# graduation_project.net
KiCad netlist of a schematic drawn in Altium Designer
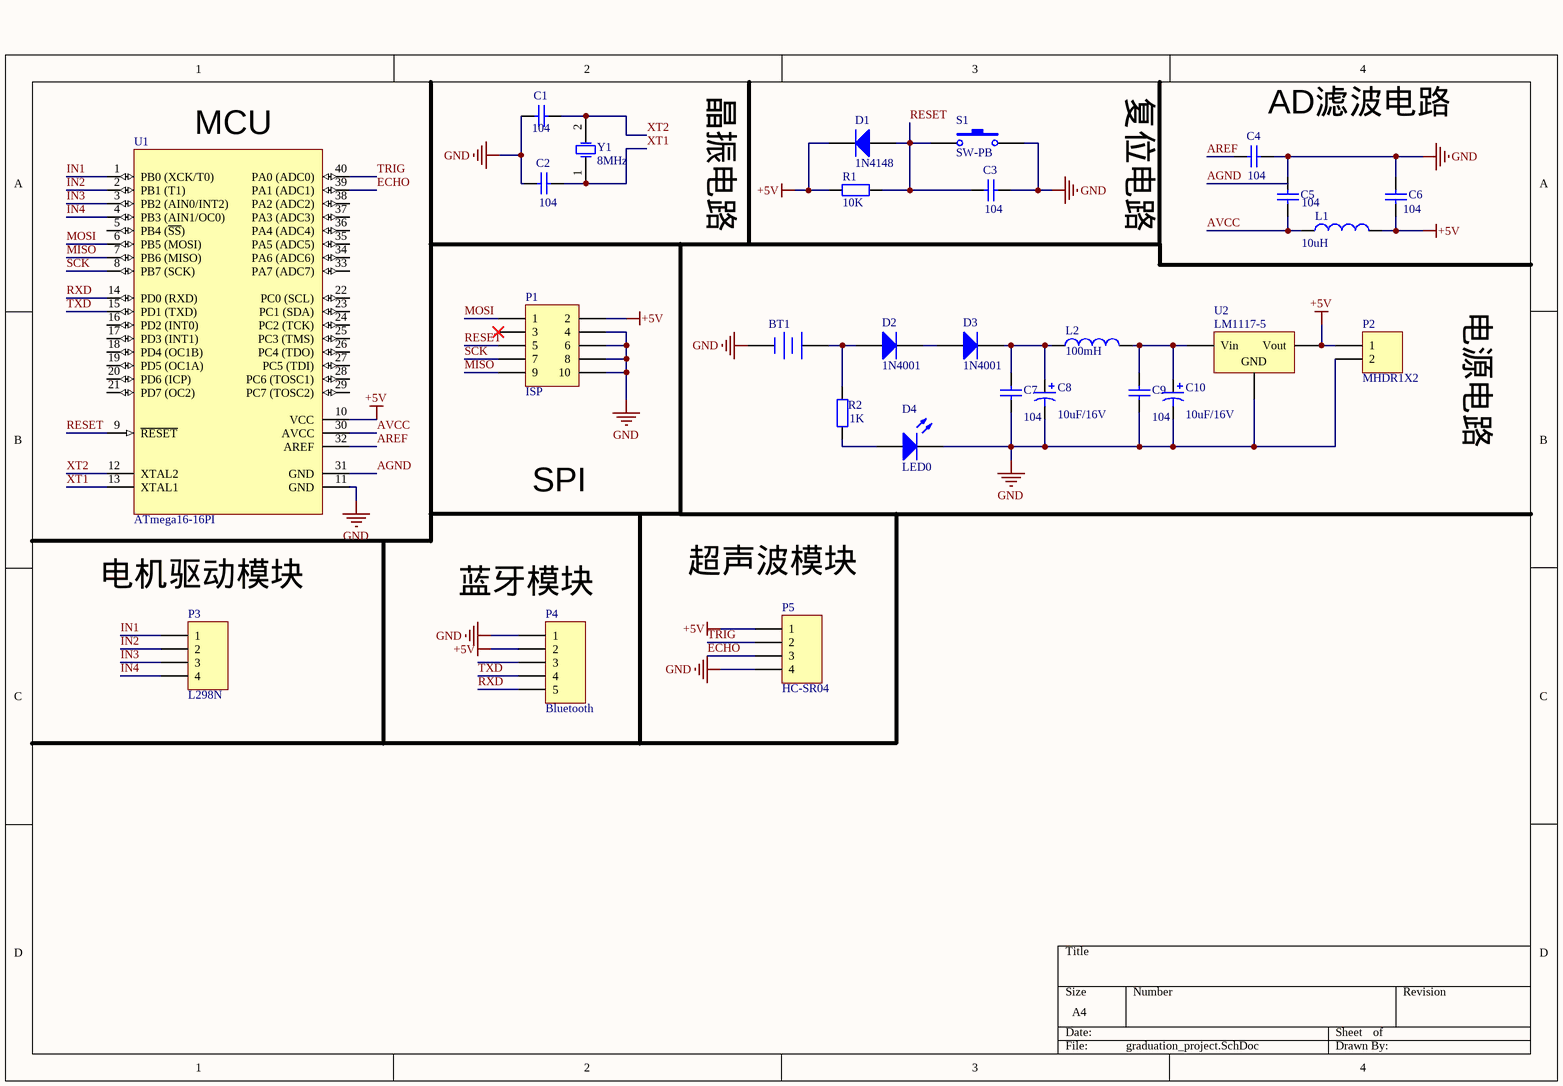
[diagram p0: graduation_project.SchDoc]

(export (version "E")
  (design (tool "Eeschema 10.0.6"))
  (components
    (comp (ref "BT1")
      (value "Battery")
      (footprint "DC10B")
      (description "Multicell Battery")
      (fields (field (name "PUBLISHER") "Altium Limited"))
      (libsource (lib "Miscellaneous Devices") (part "Battery"))
    )
    (comp (ref "C1")
      (value "104")
      (footprint "C0805")
      (description "Capacitor")
      (fields (field (name "Comment") "Cap") (field (name "PUBLISHER") "Altium Limited"))
      (libsource (lib "Miscellaneous Devices") (part "Cap"))
    )
    (comp (ref "C2")
      (value "104")
      (footprint "C0805")
      (description "Capacitor")
      (fields (field (name "Comment") "Cap") (field (name "PUBLISHER") "Altium Limited"))
      (libsource (lib "Miscellaneous Devices") (part "Cap"))
    )
    (comp (ref "C3")
      (value "104")
      (footprint "C0805")
      (description "Capacitor")
      (fields (field (name "Comment") "Cap") (field (name "PUBLISHER") "Altium Limited"))
      (libsource (lib "Miscellaneous Devices") (part "Cap"))
    )
    (comp (ref "C4")
      (value "104")
      (footprint "C0805")
      (description "Capacitor")
      (fields (field (name "Comment") "Cap") (field (name "PUBLISHER") "Altium Limited"))
      (libsource (lib "Miscellaneous Devices") (part "Cap"))
    )
    (comp (ref "C5")
      (value "104")
      (footprint "C0805")
      (description "Capacitor")
      (fields (field (name "Comment") "Cap") (field (name "PUBLISHER") "Altium Limited"))
      (libsource (lib "Miscellaneous Devices") (part "Cap"))
    )
    (comp (ref "C6")
      (value "104")
      (footprint "C0805")
      (description "Capacitor")
      (fields (field (name "Comment") "Cap") (field (name "PUBLISHER") "Altium Limited"))
      (libsource (lib "Miscellaneous Devices") (part "Cap"))
    )
    (comp (ref "C7")
      (value "104")
      (footprint "C0805")
      (description "Capacitor")
      (fields (field (name "Comment") "Cap") (field (name "PUBLISHER") "Altium Limited"))
      (libsource (lib "Miscellaneous Devices") (part "Cap"))
    )
    (comp (ref "C8")
      (value "10uF/16V")
      (footprint "CAP5*5_4")
      (description "Polarized Capacitor (Surface Mount)")
      (fields (field (name "Comment") "Cap Pol3") (field (name "PUBLISHER") "Altium Limited"))
      (libsource (lib "Miscellaneous Devices") (part "Cap Pol3"))
    )
    (comp (ref "C9")
      (value "104")
      (footprint "C0805")
      (description "Capacitor")
      (fields (field (name "Comment") "Cap") (field (name "PUBLISHER") "Altium Limited"))
      (libsource (lib "Miscellaneous Devices") (part "Cap"))
    )
    (comp (ref "C10")
      (value "10uF/16V")
      (footprint "CAP5*5_4")
      (description "Polarized Capacitor (Surface Mount)")
      (fields (field (name "Comment") "Cap Pol3") (field (name "PUBLISHER") "Altium Limited"))
      (libsource (lib "Miscellaneous Devices") (part "Cap Pol3"))
    )
    (comp (ref "D1")
      (value "1N4148")
      (footprint "1N4148-T")
      (description "Default Diode")
      (fields (field (name "PUBLISHER") "Altium Limited"))
      (libsource (lib "Miscellaneous Devices") (part "Diode"))
    )
    (comp (ref "D2")
      (value "1N4001")
      (footprint "1N4148-T")
      (description "Default Diode")
      (fields (field (name "PUBLISHER") "Altium Limited"))
      (libsource (lib "Miscellaneous Devices") (part "Diode"))
    )
    (comp (ref "D3")
      (value "1N4001")
      (footprint "1N4148-T")
      (description "Default Diode")
      (fields (field (name "PUBLISHER") "Altium Limited"))
      (libsource (lib "Miscellaneous Devices") (part "Diode"))
    )
    (comp (ref "D4")
      (value "LED0")
      (footprint "LED1206")
      (description "Typical INFRARED GaAs LED")
      (fields (field (name "PUBLISHER") "Altium Limited"))
      (libsource (lib "Miscellaneous Devices") (part "LED0"))
    )
    (comp (ref "L1")
      (value "10uH")
      (footprint "R0805")
      (description "Inductor")
      (fields (field (name "PUBLISHER") "Altium Limited"))
      (libsource (lib "Miscellaneous Devices") (part "Inductor"))
    )
    (comp (ref "L2")
      (value "100mH")
      (footprint "R0805")
      (description "Inductor")
      (fields (field (name "PUBLISHER") "Altium Limited"))
      (libsource (lib "Miscellaneous Devices") (part "Inductor"))
    )
    (comp (ref "P1")
      (value "ISP")
      (footprint "MHDR2X5")
      (description "Header, 5-Pin, Dual row")
      (fields (field (name "PUBLISHER") "Altium Limited"))
      (libsource (lib "Miscellaneous Connectors") (part "MHDR2X5"))
    )
    (comp (ref "P2")
      (value "MHDR1X2")
      (footprint "MHDR1X2")
      (description "Header, 2-Pin")
      (fields (field (name "PUBLISHER") "Altium Limited"))
      (libsource (lib "Miscellaneous Connectors") (part "MHDR1X2"))
    )
    (comp (ref "P3")
      (value "L298N")
      (footprint "MHDR1X4")
      (description "Header, 4-Pin")
      (fields (field (name "PUBLISHER") "Altium Limited"))
      (libsource (lib "Miscellaneous Connectors") (part "MHDR1X4"))
    )
    (comp (ref "P4")
      (value "Bluetooth")
      (footprint "MHDR1X5")
      (description "Header, 5-Pin")
      (fields (field (name "PUBLISHER") "Altium Limited"))
      (libsource (lib "Miscellaneous Connectors") (part "MHDR1X5"))
    )
    (comp (ref "P5")
      (value "HC-SR04")
      (footprint "MHDR1X4")
      (description "Header, 4-Pin")
      (fields (field (name "PUBLISHER") "Altium Limited"))
      (libsource (lib "Miscellaneous Connectors") (part "MHDR1X4"))
    )
    (comp (ref "R1")
      (value "10K")
      (footprint "R0805")
      (description "Resistor")
      (fields (field (name "Comment") "Res2") (field (name "PUBLISHER") "Altium Limited"))
      (libsource (lib "") (part "Res2_1"))
    )
    (comp (ref "R2")
      (value "1K")
      (footprint "R0805")
      (description "Resistor")
      (fields (field (name "Comment") "Res2") (field (name "PUBLISHER") "Altium Limited"))
      (libsource (lib "Miscellaneous Devices") (part "Res2"))
    )
    (comp (ref "S1")
      (value "SW-PB")
      (footprint "SWITCH")
      (description "Switch")
      (fields (field (name "PUBLISHER") "Altium Limited"))
      (libsource (lib "Miscellaneous Devices") (part "SW-PB"))
    )
    (comp (ref "U1")
      (value "ATmega16-16PI")
      (footprint "40P6")
      (description "8-Bit AVR Microcontroller with 16K Bytes of In-System Programmable Flash Memory")
      (fields (field (name "PUBLISHER") "Altium Limited"))
      (libsource (lib "Atmel Microcontroller 8-Bit AVR") (part "ATmega16-16PI"))
    )
    (comp (ref "U2")
      (value "LM1117-5")
      (footprint "SOT223")
      (description "Voltage Regulator")
      (fields (field (name "PUBLISHER") "Altium Limited"))
      (libsource (lib "Miscellaneous Devices") (part "Volt Reg"))
    )
    (comp (ref "Y1")
      (value "8MHz")
      (footprint "XTAL")
      (description "Crystal Oscillator")
      (fields (field (name "PUBLISHER") "Altium Limited"))
      (libsource (lib "Miscellaneous Devices") (part "XTAL"))
    )
  )
  (nets
    (net (code "1") (name "+5V") (class "Default")
      (node (ref "C6") (pin "2") (pinfunction "2_2") (pintype "passive"))
      (node (ref "D1") (pin "2") (pinfunction "K_2") (pintype "passive"))
      (node (ref "L1") (pin "2") (pinfunction "2_2") (pintype "passive"))
      (node (ref "P1") (pin "2") (pinfunction "2_2") (pintype "passive"))
      (node (ref "P2") (pin "1") (pinfunction "1_1") (pintype "passive"))
      (node (ref "P4") (pin "2") (pinfunction "2_2") (pintype "passive"))
      (node (ref "P5") (pin "1") (pinfunction "1_1") (pintype "passive"))
      (node (ref "R1") (pin "1") (pinfunction "1_1") (pintype "passive"))
      (node (ref "U1") (pin "10") (pinfunction "VCC_10") (pintype "power_in"))
      (node (ref "U2") (pin "3") (pinfunction "Vout_3") (pintype "passive"))
    )
    (net (code "2") (name "/AGND") (class "Default")
      (node (ref "U1") (pin "31") (pinfunction "GND_31") (pintype "power_in"))
    )
    (net (code "3") (name "/AREF") (class "Default")
      (node (ref "C4") (pin "2") (pinfunction "2_2") (pintype "passive"))
      (node (ref "U1") (pin "32") (pinfunction "AREF_32") (pintype "passive"))
    )
    (net (code "4") (name "/AVCC") (class "Default")
      (node (ref "C5") (pin "2") (pinfunction "2_2") (pintype "passive"))
      (node (ref "L1") (pin "1") (pinfunction "1_1") (pintype "passive"))
      (node (ref "U1") (pin "30") (pinfunction "AVCC_30") (pintype "power_in"))
    )
    (net (code "5") (name "/ECHO") (class "Default")
      (node (ref "P5") (pin "3") (pinfunction "3_3") (pintype "passive"))
      (node (ref "U1") (pin "39") (pinfunction "PA1_(ADC1)_39") (pintype "bidirectional"))
    )
    (net (code "6") (name "/IN1") (class "Default")
      (node (ref "P3") (pin "1") (pinfunction "1_1") (pintype "passive"))
      (node (ref "U1") (pin "1") (pinfunction "PB0_(XCK/T0)_1") (pintype "bidirectional"))
    )
    (net (code "7") (name "/IN2") (class "Default")
      (node (ref "P3") (pin "2") (pinfunction "2_2") (pintype "passive"))
      (node (ref "U1") (pin "2") (pinfunction "PB1_(T1)_2") (pintype "bidirectional"))
    )
    (net (code "8") (name "/IN3") (class "Default")
      (node (ref "P3") (pin "3") (pinfunction "3_3") (pintype "passive"))
      (node (ref "U1") (pin "3") (pinfunction "PB2_(AIN0/INT2)_3") (pintype "bidirectional"))
    )
    (net (code "9") (name "/IN4") (class "Default")
      (node (ref "P3") (pin "4") (pinfunction "4_4") (pintype "passive"))
      (node (ref "U1") (pin "4") (pinfunction "PB3_(AIN1/OC0)_4") (pintype "bidirectional"))
    )
    (net (code "10") (name "/MISO") (class "Default")
      (node (ref "P1") (pin "9") (pinfunction "9_9") (pintype "passive"))
      (node (ref "U1") (pin "7") (pinfunction "PB6_(MISO)_7") (pintype "bidirectional"))
    )
    (net (code "11") (name "/MOSI") (class "Default")
      (node (ref "P1") (pin "1") (pinfunction "1_1") (pintype "passive"))
      (node (ref "U1") (pin "6") (pinfunction "PB5_(MOSI)_6") (pintype "bidirectional"))
    )
    (net (code "12") (name "/RESET") (class "Default")
      (node (ref "C3") (pin "1") (pinfunction "1_1") (pintype "passive"))
      (node (ref "D1") (pin "1") (pinfunction "A_1") (pintype "passive"))
      (node (ref "P1") (pin "5") (pinfunction "5_5") (pintype "passive"))
      (node (ref "R1") (pin "2") (pinfunction "2_2") (pintype "passive"))
      (node (ref "S1") (pin "1") (pinfunction "1_1") (pintype "passive"))
      (node (ref "U1") (pin "9") (pinfunction "~{RESET}_9") (pintype "input"))
    )
    (net (code "13") (name "/RXD") (class "Default")
      (node (ref "P4") (pin "5") (pinfunction "5_5") (pintype "passive"))
      (node (ref "U1") (pin "14") (pinfunction "PD0_(RXD)_14") (pintype "bidirectional"))
    )
    (net (code "14") (name "/SCK") (class "Default")
      (node (ref "P1") (pin "7") (pinfunction "7_7") (pintype "passive"))
      (node (ref "U1") (pin "8") (pinfunction "PB7_(SCK)_8") (pintype "bidirectional"))
    )
    (net (code "15") (name "/TRIG") (class "Default")
      (node (ref "P5") (pin "2") (pinfunction "2_2") (pintype "passive"))
      (node (ref "U1") (pin "40") (pinfunction "PA0_(ADC0)_40") (pintype "bidirectional"))
    )
    (net (code "16") (name "/TXD") (class "Default")
      (node (ref "P4") (pin "4") (pinfunction "4_4") (pintype "passive"))
      (node (ref "U1") (pin "15") (pinfunction "PD1_(TXD)_15") (pintype "bidirectional"))
    )
    (net (code "17") (name "/XT1") (class "Default")
      (node (ref "C2") (pin "2") (pinfunction "2_2") (pintype "passive"))
      (node (ref "U1") (pin "13") (pinfunction "XTAL1_13") (pintype "passive"))
      (node (ref "Y1") (pin "1") (pinfunction "OSC1_1") (pintype "passive"))
    )
    (net (code "18") (name "/XT2") (class "Default")
      (node (ref "C1") (pin "2") (pinfunction "2_2") (pintype "passive"))
      (node (ref "U1") (pin "12") (pinfunction "XTAL2_12") (pintype "passive"))
      (node (ref "Y1") (pin "2") (pinfunction "OSC2_2") (pintype "passive"))
    )
    (net (code "19") (name "GND") (class "Default")
      (node (ref "BT1") (pin "2") (pinfunction "-_2") (pintype "passive"))
      (node (ref "C1") (pin "1") (pinfunction "1_1") (pintype "passive"))
      (node (ref "C10") (pin "2") (pinfunction "2_2") (pintype "passive"))
      (node (ref "C2") (pin "1") (pinfunction "1_1") (pintype "passive"))
      (node (ref "C3") (pin "2") (pinfunction "2_2") (pintype "passive"))
      (node (ref "C4") (pin "1") (pinfunction "1_1") (pintype "passive"))
      (node (ref "C5") (pin "1") (pinfunction "1_1") (pintype "passive"))
      (node (ref "C6") (pin "1") (pinfunction "1_1") (pintype "passive"))
      (node (ref "C7") (pin "1") (pinfunction "1_1") (pintype "passive"))
      (node (ref "C8") (pin "2") (pinfunction "2_2") (pintype "passive"))
      (node (ref "C9") (pin "1") (pinfunction "1_1") (pintype "passive"))
      (node (ref "D4") (pin "2") (pinfunction "K_2") (pintype "passive"))
      (node (ref "P1") (pin "10") (pinfunction "10_10") (pintype "passive"))
      (node (ref "P1") (pin "4") (pinfunction "4_4") (pintype "passive"))
      (node (ref "P1") (pin "6") (pinfunction "6_6") (pintype "passive"))
      (node (ref "P1") (pin "8") (pinfunction "8_8") (pintype "passive"))
      (node (ref "P2") (pin "2") (pinfunction "2_2") (pintype "passive"))
      (node (ref "P4") (pin "1") (pinfunction "1_1") (pintype "passive"))
      (node (ref "P5") (pin "4") (pinfunction "4_4") (pintype "passive"))
      (node (ref "S1") (pin "2") (pinfunction "2_2") (pintype "passive"))
      (node (ref "U1") (pin "11") (pinfunction "GND_11") (pintype "power_in"))
      (node (ref "U2") (pin "2") (pinfunction "GND_2") (pintype "passive"))
    )
    (net (code "20") (name "Net-(BT1-+)") (class "Default")
      (node (ref "BT1") (pin "1") (pinfunction "+_1") (pintype "passive"))
      (node (ref "D2") (pin "1") (pinfunction "A_1") (pintype "passive"))
      (node (ref "R2") (pin "1") (pinfunction "1_1") (pintype "passive"))
    )
    (net (code "21") (name "Net-(D2-K)") (class "Default")
      (node (ref "D2") (pin "2") (pinfunction "K_2") (pintype "passive"))
      (node (ref "D3") (pin "1") (pinfunction "A_1") (pintype "passive"))
    )
    (net (code "22") (name "Net-(D3-K)") (class "Default")
      (node (ref "C7") (pin "2") (pinfunction "2_2") (pintype "passive"))
      (node (ref "C8") (pin "1") (pinfunction "1_1") (pintype "passive"))
      (node (ref "D3") (pin "2") (pinfunction "K_2") (pintype "passive"))
      (node (ref "L2") (pin "1") (pinfunction "1_1") (pintype "passive"))
    )
    (net (code "23") (name "Net-(D4-A)") (class "Default")
      (node (ref "D4") (pin "1") (pinfunction "A_1") (pintype "passive"))
      (node (ref "R2") (pin "2") (pinfunction "2_2") (pintype "passive"))
    )
    (net (code "24") (name "Net-(U2-Vin)") (class "Default")
      (node (ref "C10") (pin "1") (pinfunction "1_1") (pintype "passive"))
      (node (ref "C9") (pin "2") (pinfunction "2_2") (pintype "passive"))
      (node (ref "L2") (pin "2") (pinfunction "2_2") (pintype "passive"))
      (node (ref "U2") (pin "1") (pinfunction "Vin_1") (pintype "passive"))
    )
    (net (code "25") (name "unconnected-(P1-Pad3)") (class "Default")
      (node (ref "P1") (pin "3") (pinfunction "3_3") (pintype "passive+no_connect"))
    )
    (net (code "26") (name "unconnected-(P4-Pad3)") (class "Default")
      (node (ref "P4") (pin "3") (pinfunction "3_3") (pintype "passive"))
    )
    (net (code "27") (name "unconnected-(U1-PA2_(ADC2)-Pad38)") (class "Default")
      (node (ref "U1") (pin "38") (pinfunction "PA2_(ADC2)_38") (pintype "bidirectional"))
    )
    (net (code "28") (name "unconnected-(U1-PA3_(ADC3)-Pad37)") (class "Default")
      (node (ref "U1") (pin "37") (pinfunction "PA3_(ADC3)_37") (pintype "bidirectional"))
    )
    (net (code "29") (name "unconnected-(U1-PA4_(ADC4)-Pad36)") (class "Default")
      (node (ref "U1") (pin "36") (pinfunction "PA4_(ADC4)_36") (pintype "bidirectional"))
    )
    (net (code "30") (name "unconnected-(U1-PA5_(ADC5)-Pad35)") (class "Default")
      (node (ref "U1") (pin "35") (pinfunction "PA5_(ADC5)_35") (pintype "bidirectional"))
    )
    (net (code "31") (name "unconnected-(U1-PA6_(ADC6)-Pad34)") (class "Default")
      (node (ref "U1") (pin "34") (pinfunction "PA6_(ADC6)_34") (pintype "bidirectional"))
    )
    (net (code "32") (name "unconnected-(U1-PA7_(ADC7)-Pad33)") (class "Default")
      (node (ref "U1") (pin "33") (pinfunction "PA7_(ADC7)_33") (pintype "bidirectional"))
    )
    (net (code "33") (name "unconnected-(U1-PB4_(~{SS})-Pad5)") (class "Default")
      (node (ref "U1") (pin "5") (pinfunction "PB4_(~{SS})_5") (pintype "bidirectional"))
    )
    (net (code "34") (name "unconnected-(U1-PC0_(SCL)-Pad22)") (class "Default")
      (node (ref "U1") (pin "22") (pinfunction "PC0_(SCL)_22") (pintype "bidirectional"))
    )
    (net (code "35") (name "unconnected-(U1-PC1_(SDA)-Pad23)") (class "Default")
      (node (ref "U1") (pin "23") (pinfunction "PC1_(SDA)_23") (pintype "bidirectional"))
    )
    (net (code "36") (name "unconnected-(U1-PC2_(TCK)-Pad24)") (class "Default")
      (node (ref "U1") (pin "24") (pinfunction "PC2_(TCK)_24") (pintype "bidirectional"))
    )
    (net (code "37") (name "unconnected-(U1-PC3_(TMS)-Pad25)") (class "Default")
      (node (ref "U1") (pin "25") (pinfunction "PC3_(TMS)_25") (pintype "bidirectional"))
    )
    (net (code "38") (name "unconnected-(U1-PC4_(TDO)-Pad26)") (class "Default")
      (node (ref "U1") (pin "26") (pinfunction "PC4_(TDO)_26") (pintype "bidirectional"))
    )
    (net (code "39") (name "unconnected-(U1-PC5_(TDI)-Pad27)") (class "Default")
      (node (ref "U1") (pin "27") (pinfunction "PC5_(TDI)_27") (pintype "bidirectional"))
    )
    (net (code "40") (name "unconnected-(U1-PC6_(TOSC1)-Pad28)") (class "Default")
      (node (ref "U1") (pin "28") (pinfunction "PC6_(TOSC1)_28") (pintype "bidirectional"))
    )
    (net (code "41") (name "unconnected-(U1-PC7_(TOSC2)-Pad29)") (class "Default")
      (node (ref "U1") (pin "29") (pinfunction "PC7_(TOSC2)_29") (pintype "bidirectional"))
    )
    (net (code "42") (name "unconnected-(U1-PD2_(INT0)-Pad16)") (class "Default")
      (node (ref "U1") (pin "16") (pinfunction "PD2_(INT0)_16") (pintype "bidirectional"))
    )
    (net (code "43") (name "unconnected-(U1-PD3_(INT1)-Pad17)") (class "Default")
      (node (ref "U1") (pin "17") (pinfunction "PD3_(INT1)_17") (pintype "bidirectional"))
    )
    (net (code "44") (name "unconnected-(U1-PD4_(OC1B)-Pad18)") (class "Default")
      (node (ref "U1") (pin "18") (pinfunction "PD4_(OC1B)_18") (pintype "bidirectional"))
    )
    (net (code "45") (name "unconnected-(U1-PD5_(OC1A)-Pad19)") (class "Default")
      (node (ref "U1") (pin "19") (pinfunction "PD5_(OC1A)_19") (pintype "bidirectional"))
    )
    (net (code "46") (name "unconnected-(U1-PD6_(ICP)-Pad20)") (class "Default")
      (node (ref "U1") (pin "20") (pinfunction "PD6_(ICP)_20") (pintype "bidirectional"))
    )
    (net (code "47") (name "unconnected-(U1-PD7_(OC2)-Pad21)") (class "Default")
      (node (ref "U1") (pin "21") (pinfunction "PD7_(OC2)_21") (pintype "bidirectional"))
    )
  )
)
